# pdm_1-rev0.net
KiCad netlist of a schematic drawn in EAGLE
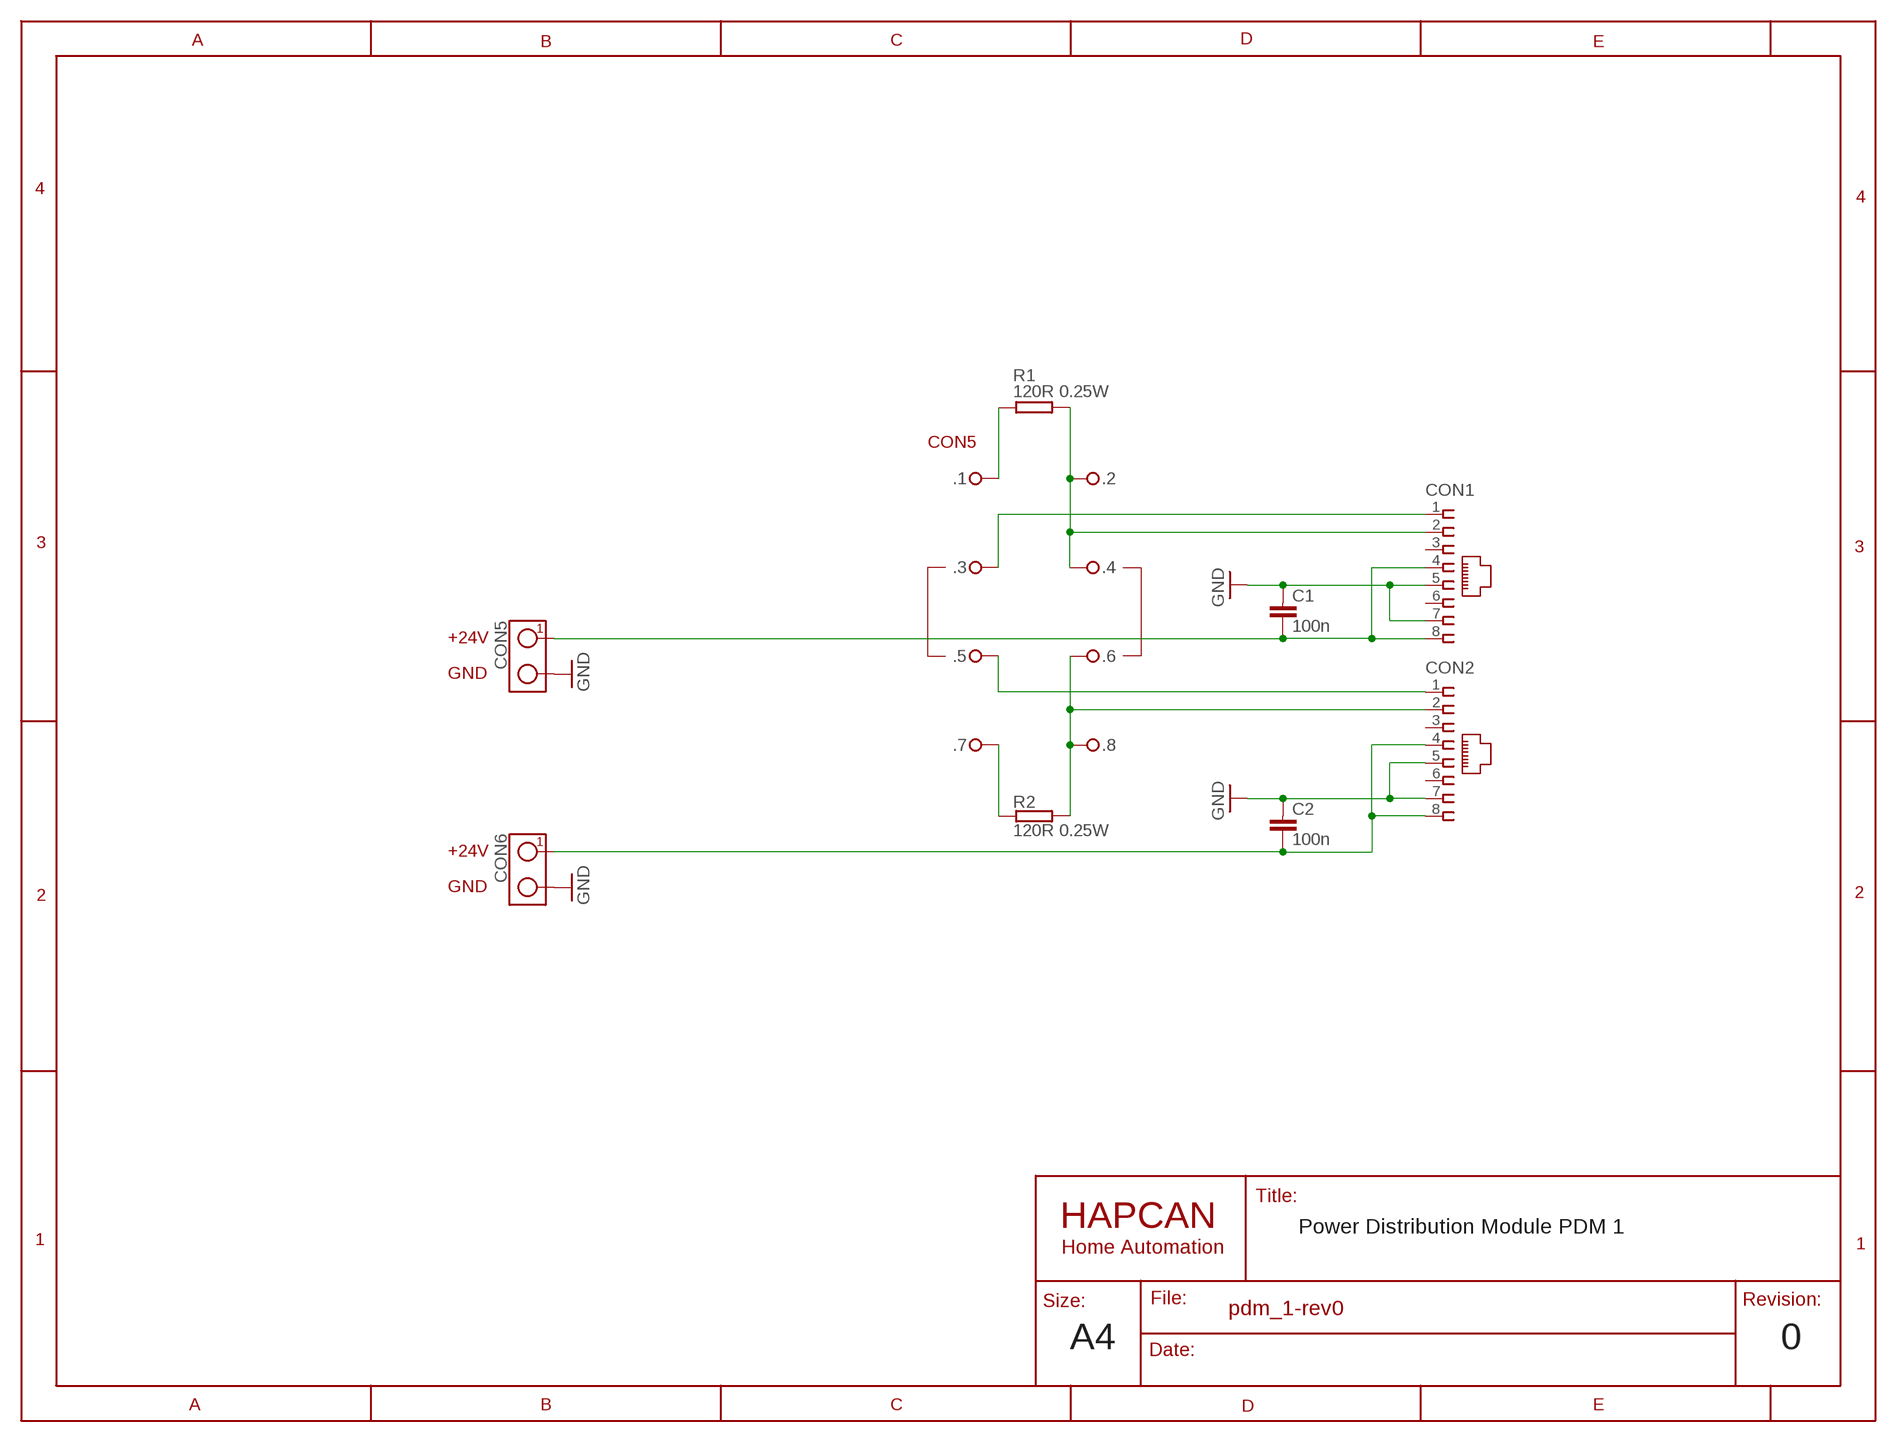
[diagram p0: schematic, sheet 1]

(export (version "E")
  (design (tool "Eeschema 10.0.6"))
  (components
    (comp (ref ".")
      (value "2x4")
      (footprint "eagle-import:HEADER-2X4")
      (libsource (lib "eagle-import") (part "HEADER2X4_NORMAL"))
    )
    (comp (ref "C1")
      (value "100n")
      (footprint "eagle-import:0805")
      (libsource (lib "eagle-import") (part "CAPACITOR0805"))
    )
    (comp (ref "C2")
      (value "100n")
      (footprint "eagle-import:0805")
      (libsource (lib "eagle-import") (part "CAPACITOR0805"))
    )
    (comp (ref "CON1")
      (value "RJ45-SOCKET")
      (footprint "eagle-import:RJ45-PCB-SOCKET")
      (libsource (lib "eagle-import") (part "RJ45-SOCKET"))
    )
    (comp (ref "CON2")
      (value "RJ45-SOCKET")
      (footprint "eagle-import:RJ45-PCB-SOCKET")
      (libsource (lib "eagle-import") (part "RJ45-SOCKET"))
    )
    (comp (ref "CON5")
      (value "TERMINAL-2-7.5X10.5MM")
      (footprint "eagle-import:ARK2-7.5X10.5MM")
      (libsource (lib "eagle-import") (part "TERMINAL-2-7.5X10.5MM"))
    )
    (comp (ref "CON6")
      (value "TERMINAL-2-7.5X10.5MM")
      (footprint "eagle-import:ARK2-7.5X10.5MM")
      (libsource (lib "eagle-import") (part "TERMINAL-2-7.5X10.5MM"))
    )
    (comp (ref "R1")
      (value "120R 0.25W")
      (footprint "eagle-import:2010")
      (libsource (lib "eagle-import") (part "RESISTOR2010"))
    )
    (comp (ref "R2")
      (value "120R 0.25W")
      (footprint "eagle-import:2010")
      (libsource (lib "eagle-import") (part "RESISTOR2010"))
    )
  )
  (nets
    (net (code "1") (name "GND") (class "Default")
      (node (ref "C1") (pin "1") (pinfunction "1_1") (pintype "passive"))
      (node (ref "C2") (pin "1") (pinfunction "1_1") (pintype "passive"))
      (node (ref "CON1") (pin "5") (pinfunction "5_5") (pintype "passive"))
      (node (ref "CON1") (pin "7") (pinfunction "7_7") (pintype "passive"))
      (node (ref "CON2") (pin "5") (pinfunction "5_5") (pintype "passive"))
      (node (ref "CON2") (pin "7") (pinfunction "7_7") (pintype "passive"))
      (node (ref "CON5") (pin "2") (pinfunction "2_2") (pintype "passive"))
      (node (ref "CON6") (pin "2") (pinfunction "2_2") (pintype "passive"))
    )
    (net (code "2") (name "Net-(.A-S)") (class "Default")
      (node (ref ".") (pin "1") (pinfunction "S_1") (pintype "passive"))
      (node (ref "R1") (pin "1") (pinfunction "1_1") (pintype "passive"))
    )
    (net (code "3") (name "Net-(.B-S)") (class "Default")
      (node (ref ".") (pin "2") (pinfunction "S_2") (pintype "passive"))
      (node (ref ".") (pin "4") (pinfunction "S_4") (pintype "passive"))
      (node (ref "CON1") (pin "2") (pinfunction "2_2") (pintype "passive"))
      (node (ref "R1") (pin "2") (pinfunction "2_2") (pintype "passive"))
    )
    (net (code "4") (name "Net-(.C-S)") (class "Default")
      (node (ref ".") (pin "3") (pinfunction "S_3") (pintype "passive"))
      (node (ref "CON1") (pin "1") (pinfunction "1_1") (pintype "passive"))
    )
    (net (code "5") (name "Net-(.E-S)") (class "Default")
      (node (ref ".") (pin "5") (pinfunction "S_5") (pintype "passive"))
      (node (ref "CON2") (pin "1") (pinfunction "1_1") (pintype "passive"))
    )
    (net (code "6") (name "Net-(.F-S)") (class "Default")
      (node (ref ".") (pin "6") (pinfunction "S_6") (pintype "passive"))
      (node (ref ".") (pin "8") (pinfunction "S_8") (pintype "passive"))
      (node (ref "CON2") (pin "2") (pinfunction "2_2") (pintype "passive"))
      (node (ref "R2") (pin "2") (pinfunction "2_2") (pintype "passive"))
    )
    (net (code "7") (name "Net-(.G-S)") (class "Default")
      (node (ref ".") (pin "7") (pinfunction "S_7") (pintype "passive"))
      (node (ref "R2") (pin "1") (pinfunction "1_1") (pintype "passive"))
    )
    (net (code "8") (name "Net-(C1-Pad2)") (class "Default")
      (node (ref "C1") (pin "2") (pinfunction "2_2") (pintype "passive"))
      (node (ref "CON1") (pin "4") (pinfunction "4_4") (pintype "passive"))
      (node (ref "CON1") (pin "8") (pinfunction "8_8") (pintype "passive"))
      (node (ref "CON5") (pin "1") (pinfunction "1_1") (pintype "passive"))
    )
    (net (code "9") (name "Net-(C2-Pad2)") (class "Default")
      (node (ref "C2") (pin "2") (pinfunction "2_2") (pintype "passive"))
      (node (ref "CON2") (pin "4") (pinfunction "4_4") (pintype "passive"))
      (node (ref "CON2") (pin "8") (pinfunction "8_8") (pintype "passive"))
      (node (ref "CON6") (pin "1") (pinfunction "1_1") (pintype "passive"))
    )
    (net (code "10") (name "unconnected-(CON1-Pad3)") (class "Default")
      (node (ref "CON1") (pin "3") (pinfunction "3_3") (pintype "passive"))
    )
    (net (code "11") (name "unconnected-(CON1-Pad6)") (class "Default")
      (node (ref "CON1") (pin "6") (pinfunction "6_6") (pintype "passive"))
    )
    (net (code "12") (name "unconnected-(CON2-Pad3)") (class "Default")
      (node (ref "CON2") (pin "3") (pinfunction "3_3") (pintype "passive"))
    )
    (net (code "13") (name "unconnected-(CON2-Pad6)") (class "Default")
      (node (ref "CON2") (pin "6") (pinfunction "6_6") (pintype "passive"))
    )
  )
)
